# placa_teste_av.net
KiCad netlist of a schematic drawn in EAGLE
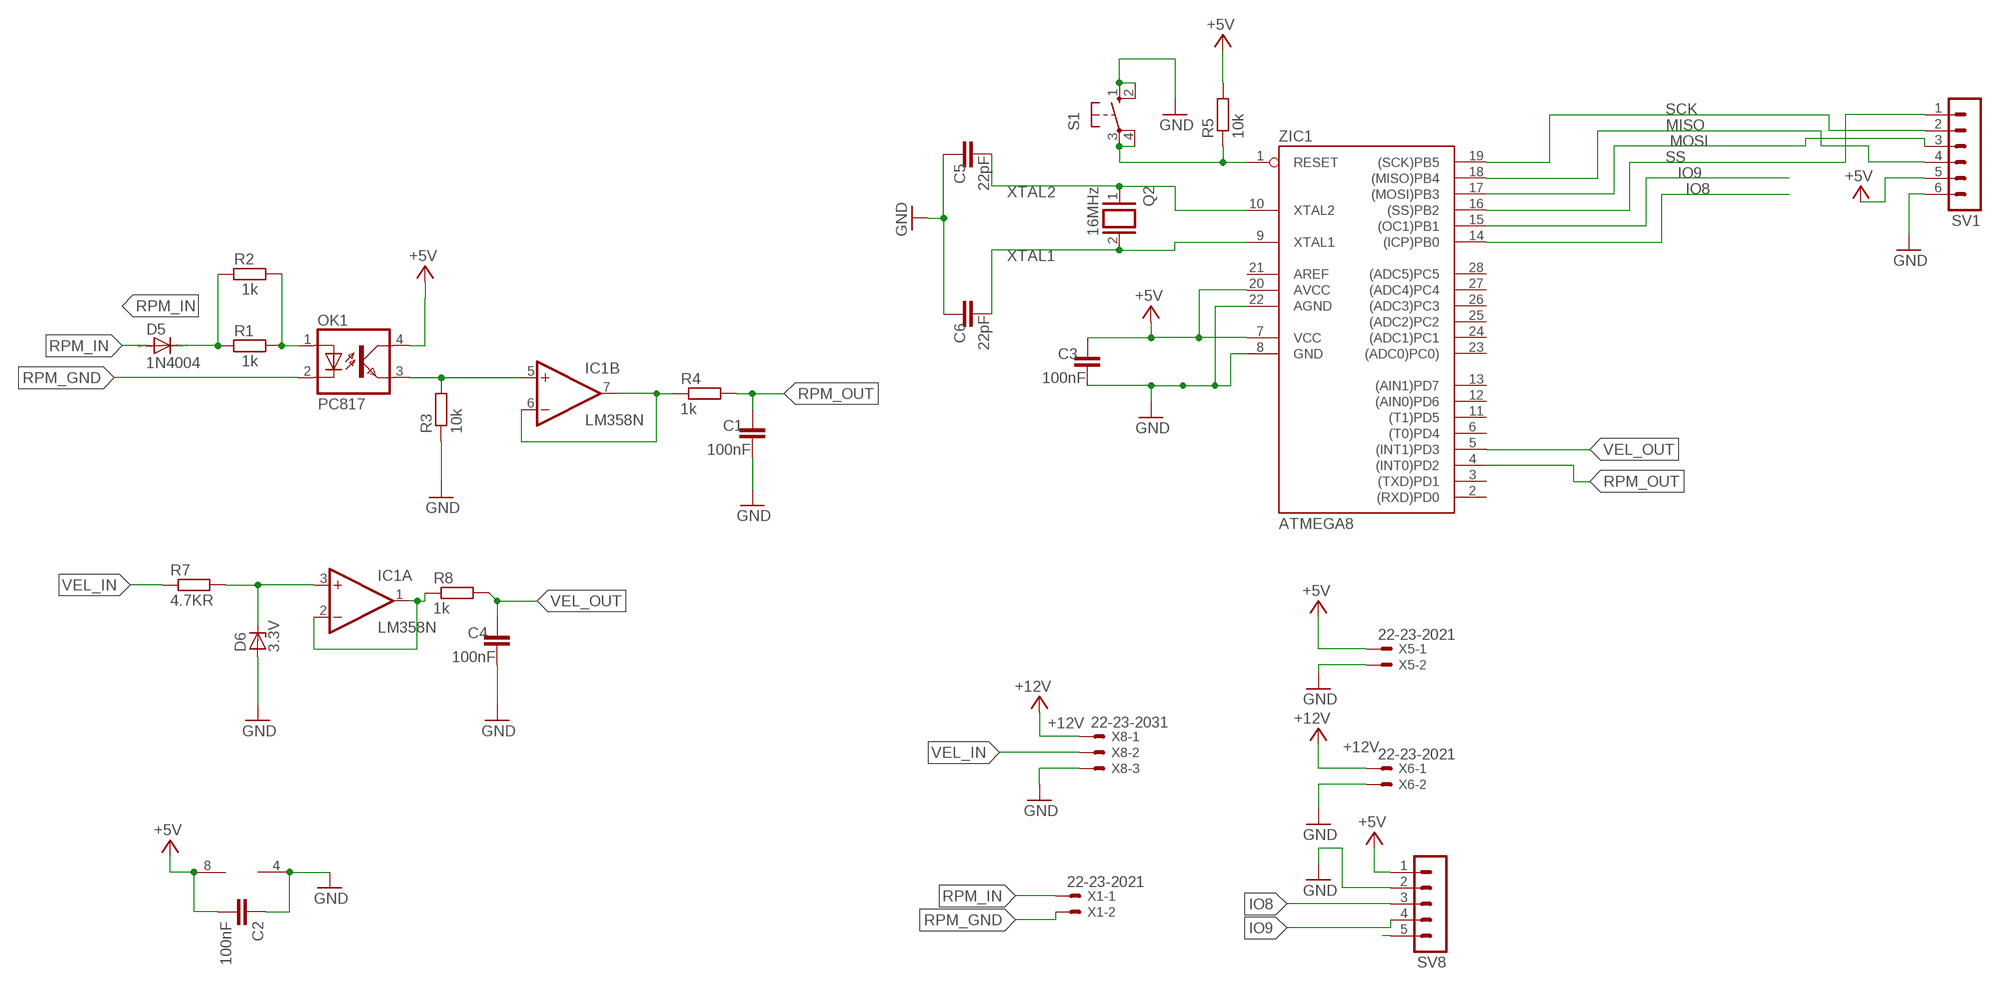
[diagram p0: schematic, sheet 1]

(export (version "E")
  (design (tool "Eeschema 10.0.6"))
  (components
    (comp (ref "C1")
      (value "100nF")
      (footprint "eagle-import:C5B2.5")
      (libsource (lib "eagle-import") (part "C5/2.5"))
    )
    (comp (ref "C2")
      (value "100nF")
      (footprint "eagle-import:C2.5-3")
      (libsource (lib "eagle-import") (part "C2,5-3"))
    )
    (comp (ref "C3")
      (value "100nF")
      (footprint "eagle-import:C5B2.5")
      (libsource (lib "eagle-import") (part "C5/2.5"))
    )
    (comp (ref "C4")
      (value "100nF")
      (footprint "eagle-import:C5B2.5")
      (libsource (lib "eagle-import") (part "C5/2.5"))
    )
    (comp (ref "C5")
      (value "22pF")
      (footprint "eagle-import:C5B2.5")
      (libsource (lib "eagle-import") (part "C5/2.5"))
    )
    (comp (ref "C6")
      (value "22pF")
      (footprint "eagle-import:C5B2.5")
      (libsource (lib "eagle-import") (part "C5/2.5"))
    )
    (comp (ref "D5")
      (value "1N4004")
      (footprint "eagle-import:DO41-10")
      (libsource (lib "eagle-import") (part "1N4004"))
    )
    (comp (ref "D6")
      (value "3.3V")
      (footprint "eagle-import:DO34Z7")
      (libsource (lib "eagle-import") (part "ZENER-DIODEDO34-7"))
    )
    (comp (ref "IC1")
      (value "LM358N")
      (footprint "eagle-import:DIL08")
      (libsource (lib "eagle-import") (part "LM358N"))
    )
    (comp (ref "OK1")
      (value "PC817")
      (footprint "eagle-import:DIL04")
      (fields (field (name "MPN") "PC817X4J000F"))
      (libsource (lib "eagle-import") (part "PC817"))
    )
    (comp (ref "Q2")
      (value "16MHz")
      (footprint "eagle-import:QS")
      (libsource (lib "eagle-import") (part "XTAL/S"))
    )
    (comp (ref "R1")
      (value "1k")
      (footprint "eagle-import:0207_7")
      (libsource (lib "eagle-import") (part "R-EU_0207/7"))
    )
    (comp (ref "R2")
      (value "1k")
      (footprint "eagle-import:0207_7")
      (libsource (lib "eagle-import") (part "R-EU_0207/7"))
    )
    (comp (ref "R3")
      (value "10k")
      (footprint "eagle-import:0207_7")
      (libsource (lib "eagle-import") (part "R-EU_0207/7"))
    )
    (comp (ref "R4")
      (value "1k")
      (footprint "eagle-import:0207_7")
      (libsource (lib "eagle-import") (part "R-EU_0207/7"))
    )
    (comp (ref "R5")
      (value "10k")
      (footprint "eagle-import:0207_7")
      (libsource (lib "eagle-import") (part "R-EU_0207/7"))
    )
    (comp (ref "R7")
      (value "4.7KR")
      (footprint "eagle-import:0207_7")
      (libsource (lib "eagle-import") (part "R-EU_0207/7"))
    )
    (comp (ref "R8")
      (value "1k")
      (footprint "eagle-import:0207_7")
      (libsource (lib "eagle-import") (part "R-EU_0207/7"))
    )
    (comp (ref "S1")
      (value "10-XX")
      (footprint "eagle-import:B3F-10XX")
      (fields (field (name "MPN") "B3F-1000"))
      (libsource (lib "eagle-import") (part "10-XX"))
    )
    (comp (ref "SV1")
      (value "MA06-1")
      (footprint "eagle-import:MA06-1")
      (libsource (lib "eagle-import") (part "MA06-1"))
    )
    (comp (ref "SV8")
      (value "MA05-1")
      (footprint "eagle-import:MA05-1")
      (libsource (lib "eagle-import") (part "MA05-1"))
    )
    (comp (ref "X1")
      (value "22-23-2021")
      (footprint "eagle-import:22-23-2021")
      (fields (field (name "MF") "MOLEX"))
      (libsource (lib "eagle-import") (part "22-23-2021"))
    )
    (comp (ref "X5")
      (value "22-23-2021")
      (footprint "eagle-import:22-23-2021")
      (fields (field (name "MF") "MOLEX"))
      (libsource (lib "eagle-import") (part "22-23-2021"))
    )
    (comp (ref "X6")
      (value "22-23-2021")
      (footprint "eagle-import:22-23-2021")
      (fields (field (name "MF") "MOLEX"))
      (libsource (lib "eagle-import") (part "22-23-2021"))
    )
    (comp (ref "X8")
      (value "22-23-2031")
      (footprint "eagle-import:22-23-2031")
      (fields (field (name "MF") "MOLEX"))
      (libsource (lib "eagle-import") (part "22-23-2031"))
    )
    (comp (ref "ZIC1")
      (value "ATMEGA8")
      (footprint "eagle-import:DIL28-3")
      (libsource (lib "eagle-import") (part "AT90S4433P"))
    )
  )
  (nets
    (net (code "1") (name "+5V") (class "Default")
      (node (ref "C2") (pin "2") (pinfunction "2_2") (pintype "passive"))
      (node (ref "C3") (pin "2") (pinfunction "2_2") (pintype "passive"))
      (node (ref "IC1") (pin "8") (pinfunction "V+_8") (pintype "power_in"))
      (node (ref "OK1") (pin "4") (pinfunction "COL_4") (pintype "passive"))
      (node (ref "R5") (pin "2") (pinfunction "2_2") (pintype "passive"))
      (node (ref "SV1") (pin "5") (pinfunction "5_5") (pintype "passive"))
      (node (ref "SV8") (pin "1") (pinfunction "1_1") (pintype "passive"))
      (node (ref "X5") (pin "1") (pinfunction "S_1") (pintype "passive"))
      (node (ref "ZIC1") (pin "20") (pinfunction "AVCC_20") (pintype "power_in"))
      (node (ref "ZIC1") (pin "7") (pinfunction "VCC_7") (pintype "power_in"))
    )
    (net (code "2") (name "+12V") (class "Default")
      (node (ref "X6") (pin "1") (pinfunction "S_1") (pintype "passive"))
      (node (ref "X8") (pin "1") (pinfunction "S_1") (pintype "passive"))
    )
    (net (code "3") (name "/MISO") (class "Default")
      (node (ref "SV1") (pin "4") (pinfunction "4_4") (pintype "passive"))
      (node (ref "ZIC1") (pin "18") (pinfunction "(MISO)PB4_18") (pintype "bidirectional"))
    )
    (net (code "4") (name "/MOSI") (class "Default")
      (node (ref "SV1") (pin "3") (pinfunction "3_3") (pintype "passive"))
      (node (ref "ZIC1") (pin "17") (pinfunction "(MOSI)PB3_17") (pintype "bidirectional"))
    )
    (net (code "5") (name "/SCK") (class "Default")
      (node (ref "SV1") (pin "2") (pinfunction "2_2") (pintype "passive"))
      (node (ref "ZIC1") (pin "19") (pinfunction "(SCK)PB5_19") (pintype "bidirectional"))
    )
    (net (code "6") (name "/SS") (class "Default")
      (node (ref "SV1") (pin "1") (pinfunction "1_1") (pintype "passive"))
      (node (ref "ZIC1") (pin "16") (pinfunction "(SS)PB2_16") (pintype "bidirectional"))
    )
    (net (code "7") (name "/XTAL1") (class "Default")
      (node (ref "C6") (pin "1") (pinfunction "1_1") (pintype "passive"))
      (node (ref "Q2") (pin "2") (pinfunction "2_2") (pintype "passive"))
      (node (ref "ZIC1") (pin "9") (pinfunction "XTAL1_9") (pintype "bidirectional"))
    )
    (net (code "8") (name "/XTAL2") (class "Default")
      (node (ref "C5") (pin "1") (pinfunction "1_1") (pintype "passive"))
      (node (ref "Q2") (pin "1") (pinfunction "1_1") (pintype "passive"))
      (node (ref "ZIC1") (pin "10") (pinfunction "XTAL2_10") (pintype "bidirectional"))
    )
    (net (code "9") (name "GND") (class "Default")
      (node (ref "C1") (pin "1") (pinfunction "1_1") (pintype "passive"))
      (node (ref "C2") (pin "1") (pinfunction "1_1") (pintype "passive"))
      (node (ref "C3") (pin "1") (pinfunction "1_1") (pintype "passive"))
      (node (ref "C4") (pin "1") (pinfunction "1_1") (pintype "passive"))
      (node (ref "C5") (pin "2") (pinfunction "2_2") (pintype "passive"))
      (node (ref "C6") (pin "2") (pinfunction "2_2") (pintype "passive"))
      (node (ref "D6") (pin "A") (pinfunction "A_A") (pintype "passive"))
      (node (ref "IC1") (pin "4") (pinfunction "V-_4") (pintype "power_in"))
      (node (ref "R3") (pin "1") (pinfunction "1_1") (pintype "passive"))
      (node (ref "S1") (pin "1") (pinfunction "S_1") (pintype "passive"))
      (node (ref "S1") (pin "2") (pinfunction "S1_2") (pintype "passive"))
      (node (ref "SV1") (pin "6") (pinfunction "6_6") (pintype "passive"))
      (node (ref "SV8") (pin "2") (pinfunction "2_2") (pintype "passive"))
      (node (ref "X5") (pin "2") (pinfunction "S_2") (pintype "passive"))
      (node (ref "X6") (pin "2") (pinfunction "S_2") (pintype "passive"))
      (node (ref "X8") (pin "3") (pinfunction "S_3") (pintype "passive"))
      (node (ref "ZIC1") (pin "22") (pinfunction "AGND_22") (pintype "power_in"))
      (node (ref "ZIC1") (pin "8") (pinfunction "GND_8") (pintype "power_in"))
    )
    (net (code "10") (name "IO8") (class "Default")
      (node (ref "SV8") (pin "3") (pinfunction "3_3") (pintype "passive"))
      (node (ref "ZIC1") (pin "14") (pinfunction "(ICP)PB0_14") (pintype "bidirectional"))
    )
    (net (code "11") (name "IO9") (class "Default")
      (node (ref "SV8") (pin "4") (pinfunction "4_4") (pintype "passive"))
      (node (ref "ZIC1") (pin "15") (pinfunction "(OC1)PB1_15") (pintype "bidirectional"))
    )
    (net (code "12") (name "Net-(D5-PadC)") (class "Default")
      (node (ref "D5") (pin "C") (pinfunction "C_C") (pintype "passive"))
      (node (ref "R1") (pin "1") (pinfunction "1_1") (pintype "passive"))
      (node (ref "R2") (pin "1") (pinfunction "1_1") (pintype "passive"))
    )
    (net (code "13") (name "Net-(IC1A-+IN)") (class "Default")
      (node (ref "D6") (pin "C") (pinfunction "C_C") (pintype "passive"))
      (node (ref "IC1") (pin "3") (pinfunction "+IN_3") (pintype "input"))
      (node (ref "R7") (pin "2") (pinfunction "2_2") (pintype "passive"))
    )
    (net (code "14") (name "Net-(IC1A--IN)") (class "Default")
      (node (ref "IC1") (pin "1") (pinfunction "OUT_1") (pintype "output"))
      (node (ref "IC1") (pin "2") (pinfunction "-IN_2") (pintype "input"))
      (node (ref "R8") (pin "1") (pinfunction "1_1") (pintype "passive"))
    )
    (net (code "15") (name "Net-(IC1B-+IN)") (class "Default")
      (node (ref "IC1") (pin "5") (pinfunction "+IN_5") (pintype "input"))
      (node (ref "OK1") (pin "3") (pinfunction "EMIT_3") (pintype "passive"))
      (node (ref "R3") (pin "2") (pinfunction "2_2") (pintype "passive"))
    )
    (net (code "16") (name "Net-(IC1B--IN)") (class "Default")
      (node (ref "IC1") (pin "6") (pinfunction "-IN_6") (pintype "input"))
      (node (ref "IC1") (pin "7") (pinfunction "OUT_7") (pintype "output"))
      (node (ref "R4") (pin "1") (pinfunction "1_1") (pintype "passive"))
    )
    (net (code "17") (name "Net-(OK1-A)") (class "Default")
      (node (ref "OK1") (pin "1") (pinfunction "A_1") (pintype "passive"))
      (node (ref "R1") (pin "2") (pinfunction "2_2") (pintype "passive"))
      (node (ref "R2") (pin "2") (pinfunction "2_2") (pintype "passive"))
    )
    (net (code "18") (name "Net-(S1-P)") (class "Default")
      (node (ref "R5") (pin "1") (pinfunction "1_1") (pintype "passive"))
      (node (ref "S1") (pin "3") (pinfunction "P_3") (pintype "passive"))
      (node (ref "S1") (pin "4") (pinfunction "P1_4") (pintype "passive"))
      (node (ref "ZIC1") (pin "1") (pinfunction "RESET_1") (pintype "input"))
    )
    (net (code "19") (name "RPM_GND") (class "Default")
      (node (ref "OK1") (pin "2") (pinfunction "C_2") (pintype "passive"))
      (node (ref "X1") (pin "2") (pinfunction "S_2") (pintype "passive"))
    )
    (net (code "20") (name "RPM_IN") (class "Default")
      (node (ref "D5") (pin "A") (pinfunction "A_A") (pintype "passive"))
      (node (ref "X1") (pin "1") (pinfunction "S_1") (pintype "passive"))
    )
    (net (code "21") (name "RPM_OUT") (class "Default")
      (node (ref "C1") (pin "2") (pinfunction "2_2") (pintype "passive"))
      (node (ref "R4") (pin "2") (pinfunction "2_2") (pintype "passive"))
      (node (ref "ZIC1") (pin "4") (pinfunction "(INT0)PD2_4") (pintype "bidirectional"))
    )
    (net (code "22") (name "VEL_IN") (class "Default")
      (node (ref "R7") (pin "1") (pinfunction "1_1") (pintype "passive"))
      (node (ref "X8") (pin "2") (pinfunction "S_2") (pintype "passive"))
    )
    (net (code "23") (name "VEL_OUT") (class "Default")
      (node (ref "C4") (pin "2") (pinfunction "2_2") (pintype "passive"))
      (node (ref "R8") (pin "2") (pinfunction "2_2") (pintype "passive"))
      (node (ref "ZIC1") (pin "5") (pinfunction "(INT1)PD3_5") (pintype "bidirectional"))
    )
    (net (code "24") (name "unconnected-(SV8-Pad5)") (class "Default")
      (node (ref "SV8") (pin "5") (pinfunction "5_5") (pintype "passive"))
    )
    (net (code "25") (name "unconnected-(ZIC1-(ADC0)PC0)-Pad23)") (class "Default")
      (node (ref "ZIC1") (pin "23") (pinfunction "(ADC0)PC0)_23") (pintype "bidirectional"))
    )
    (net (code "26") (name "unconnected-(ZIC1-(ADC1)PC1-Pad24)") (class "Default")
      (node (ref "ZIC1") (pin "24") (pinfunction "(ADC1)PC1_24") (pintype "bidirectional"))
    )
    (net (code "27") (name "unconnected-(ZIC1-(ADC2)PC2-Pad25)") (class "Default")
      (node (ref "ZIC1") (pin "25") (pinfunction "(ADC2)PC2_25") (pintype "bidirectional"))
    )
    (net (code "28") (name "unconnected-(ZIC1-(ADC3)PC3-Pad26)") (class "Default")
      (node (ref "ZIC1") (pin "26") (pinfunction "(ADC3)PC3_26") (pintype "bidirectional"))
    )
    (net (code "29") (name "unconnected-(ZIC1-(ADC4)PC4-Pad27)") (class "Default")
      (node (ref "ZIC1") (pin "27") (pinfunction "(ADC4)PC4_27") (pintype "bidirectional"))
    )
    (net (code "30") (name "unconnected-(ZIC1-(ADC5)PC5-Pad28)") (class "Default")
      (node (ref "ZIC1") (pin "28") (pinfunction "(ADC5)PC5_28") (pintype "bidirectional"))
    )
    (net (code "31") (name "unconnected-(ZIC1-(AIN0)PD6-Pad12)") (class "Default")
      (node (ref "ZIC1") (pin "12") (pinfunction "(AIN0)PD6_12") (pintype "bidirectional"))
    )
    (net (code "32") (name "unconnected-(ZIC1-(AIN1)PD7-Pad13)") (class "Default")
      (node (ref "ZIC1") (pin "13") (pinfunction "(AIN1)PD7_13") (pintype "bidirectional"))
    )
    (net (code "33") (name "unconnected-(ZIC1-(RXD)PD0-Pad2)") (class "Default")
      (node (ref "ZIC1") (pin "2") (pinfunction "(RXD)PD0_2") (pintype "bidirectional"))
    )
    (net (code "34") (name "unconnected-(ZIC1-(T0)PD4-Pad6)") (class "Default")
      (node (ref "ZIC1") (pin "6") (pinfunction "(T0)PD4_6") (pintype "bidirectional"))
    )
    (net (code "35") (name "unconnected-(ZIC1-(T1)PD5-Pad11)") (class "Default")
      (node (ref "ZIC1") (pin "11") (pinfunction "(T1)PD5_11") (pintype "bidirectional"))
    )
    (net (code "36") (name "unconnected-(ZIC1-(TXD)PD1-Pad3)") (class "Default")
      (node (ref "ZIC1") (pin "3") (pinfunction "(TXD)PD1_3") (pintype "bidirectional"))
    )
    (net (code "37") (name "unconnected-(ZIC1-AREF-Pad21)") (class "Default")
      (node (ref "ZIC1") (pin "21") (pinfunction "AREF_21") (pintype "passive"))
    )
  )
)
